# MAIN_SCH.net
KiCad netlist of a schematic drawn in Altium Designer
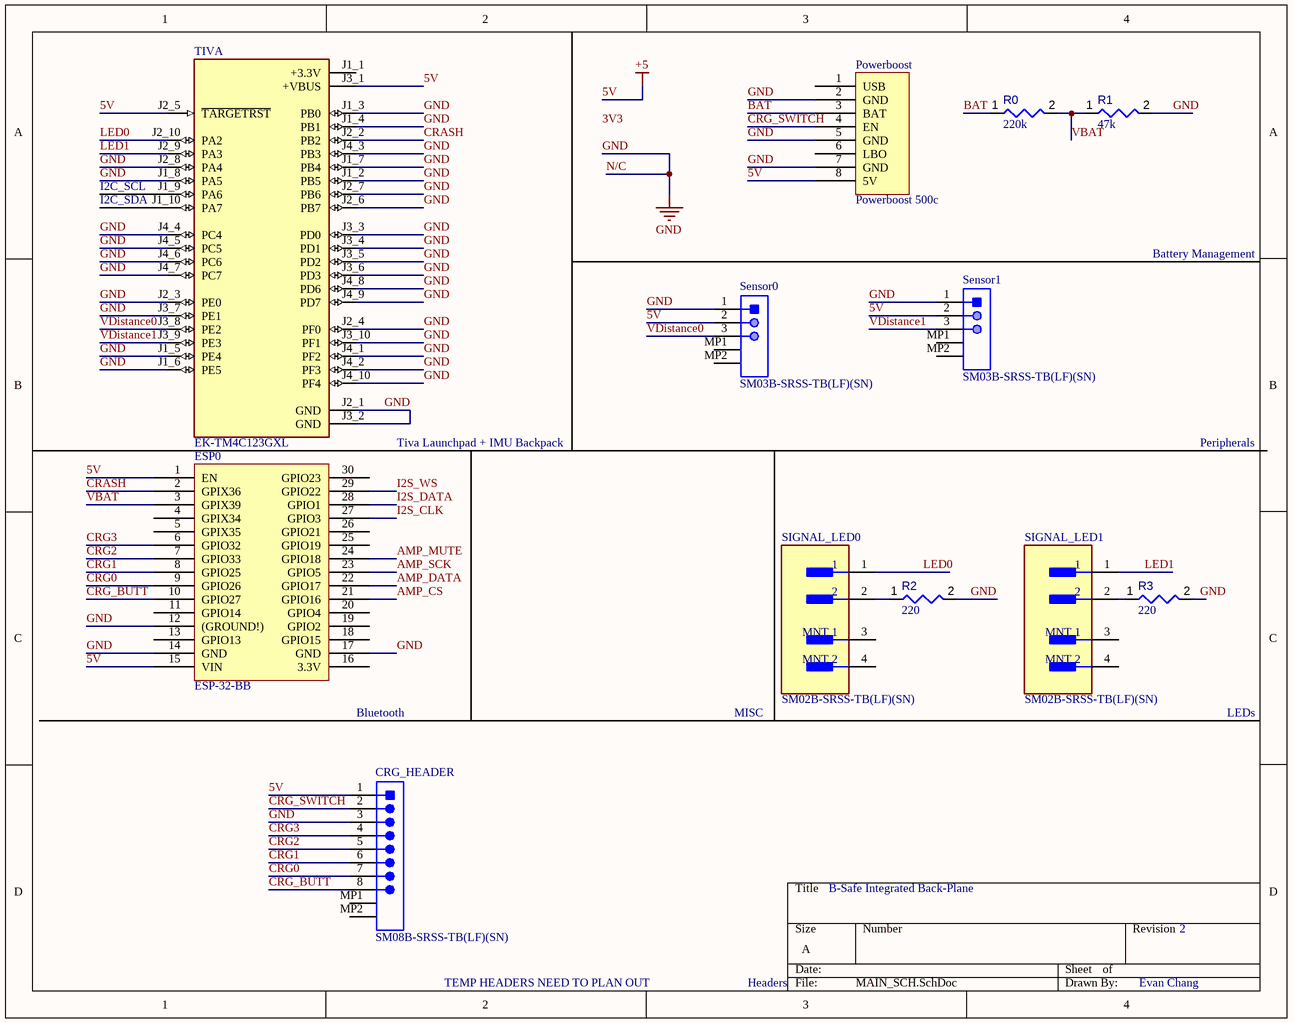
[diagram p0: MAIN_SCH.SchDoc]

(export (version "E")
  (design (tool "Eeschema 10.0.6"))
  (components
    (comp (ref "CRG_HEADER")
      (value "SM08B-SRSS-TB(LF)(SN)")
      (footprint "JST-SM08B-SRSS-TB_V")
      (description "Connector Header, Side Entry, SR Series, 8 Position, 1.00mm, 50V, Surface Mount, Tin, Natural")
      (libsource (lib "Evan Chang work on PCB") (part "CN-1P-2M-R8"))
    )
    (comp (ref "ESP0")
      (value "ESP-32-BB")
      (footprint "ESP-32-BB-Footprint-1")
      (description "Breakoutboard for ESP-32-BB")
      (libsource (lib "Evan Chang work on PCB") (part "ESP-32-BB-Symbol-1"))
    )
    (comp (ref "Powerboost")
      (value "Powerboost 500c")
      (footprint "Powerboost 500c-Footprint-1")
      (description "Breakout board component for Adafruit Powerboost 500c")
      (libsource (lib "Evan Chang work on PCB") (part "Powerboost 500c-Symbol-1"))
    )
    (comp (ref "R0")
      (value "220k")
      (footprint "RESC1005X40X25NL05T10")
      (fields (field (name "TOLERANCE") "1%") (field (name "Comment") "RC0402FR-07220KL"))
      (libsource (lib "Evan Chang work on PCB") (part "RES-2"))
    )
    (comp (ref "R1")
      (value "47k")
      (footprint "RESC1005X40X25NL05T10")
      (fields (field (name "TOLERANCE") "1%") (field (name "Comment") "RC0402FR-0747KL"))
      (libsource (lib "Evan Chang work on PCB") (part "RES-2"))
    )
    (comp (ref "R2")
      (value "220")
      (footprint "RESC1608X55X30LL20T10")
      (fields (field (name "TOLERANCE") "5%") (field (name "Comment") "RK73B1JTTD221J"))
      (libsource (lib "Evan Chang work on PCB") (part "RES-2"))
    )
    (comp (ref "R3")
      (value "220")
      (footprint "RESC1608X55X30LL20T10")
      (fields (field (name "TOLERANCE") "5%") (field (name "Comment") "RK73B1JTTD221J"))
      (libsource (lib "Evan Chang work on PCB") (part "RES-2"))
    )
    (comp (ref "Sensor0")
      (value "SM03B-SRSS-TB(LF)(SN)")
      (footprint "JST-SM03B-SRSS-TB_V")
      (description "CONN HEADER SH 3POS SIDE 1MM TIN")
      (libsource (lib "Evan Chang work on PCB") (part "CN-1P-2M-R3"))
    )
    (comp (ref "Sensor1")
      (value "SM03B-SRSS-TB(LF)(SN)")
      (footprint "JST-SM03B-SRSS-TB_V")
      (description "CONN HEADER SH 3POS SIDE 1MM TIN")
      (libsource (lib "Evan Chang work on PCB") (part "CN-1P-2M-R3"))
    )
    (comp (ref "SIGNAL_LED0")
      (value "SM02B-SRSS-TB(LF)(SN)")
      (footprint "FP-SM02B-SRSS-TB_LF_SN-0")
      (description "CONN HEADER SH 2POS SIDE 1MM TIN")
      (libsource (lib "Evan Chang work on PCB") (part "e34efe21362d63d7198b5d2c73e37bd"))
    )
    (comp (ref "SIGNAL_LED1")
      (value "SM02B-SRSS-TB(LF)(SN)")
      (footprint "FP-SM02B-SRSS-TB_LF_SN-0")
      (description "CONN HEADER SH 2POS SIDE 1MM TIN")
      (libsource (lib "Evan Chang work on PCB") (part "e34efe21362d63d7198b5d2c73e37bd"))
    )
    (comp (ref "TIVA")
      (value "EK-TM4C123GXL")
      (footprint "EK-TM4C123GXL-Footprint-1")
      (description "ARMÂ® CortexÂ®-M4F Based MCU TM4C123G LaunchPadâ„¢ Evaluation Kit")
      (fields (field (name "MF") "Texas Instruments"))
      (libsource (lib "Evan Chang work on PCB") (part "EK-TM4C123GXL"))
    )
  )
  (nets
    (net (code "1") (name "+5") (class "Default")
      (node (ref "CRG_HEADER") (pin "1") (pinfunction "1_1") (pintype "passive"))
      (node (ref "ESP0") (pin "1") (pinfunction "EN_1") (pintype "passive"))
      (node (ref "ESP0") (pin "15") (pinfunction "VIN_15") (pintype "power_in"))
      (node (ref "Powerboost") (pin "8") (pinfunction "5V_8") (pintype "power_in"))
      (node (ref "Sensor0") (pin "2") (pinfunction "2_2") (pintype "passive"))
      (node (ref "Sensor1") (pin "2") (pinfunction "2_2") (pintype "passive"))
      (node (ref "TIVA") (pin "J2_5") (pinfunction "~{TARGETRST}_J2_5") (pintype "input"))
      (node (ref "TIVA") (pin "J3_1") (pinfunction "+VBUS_J3_1") (pintype "power_in"))
    )
    (net (code "3") (name "/AMP_CS") (class "Default")
      (node (ref "ESP0") (pin "21") (pinfunction "GPIO16_21") (pintype "passive"))
    )
    (net (code "4") (name "/AMP_DATA") (class "Default")
      (node (ref "ESP0") (pin "22") (pinfunction "GPIO17_22") (pintype "passive"))
    )
    (net (code "5") (name "/AMP_MUTE") (class "Default")
      (node (ref "ESP0") (pin "24") (pinfunction "GPIO18_24") (pintype "passive"))
    )
    (net (code "6") (name "/AMP_SCK") (class "Default")
      (node (ref "ESP0") (pin "23") (pinfunction "GPIO5_23") (pintype "passive"))
    )
    (net (code "7") (name "/BAT") (class "Default")
      (node (ref "Powerboost") (pin "3") (pinfunction "BAT_3") (pintype "passive"))
      (node (ref "R0") (pin "1") (pinfunction "1_1") (pintype "passive"))
    )
    (net (code "8") (name "/CRASH") (class "Default")
      (node (ref "ESP0") (pin "2") (pinfunction "GPIX36_2") (pintype "passive"))
      (node (ref "TIVA") (pin "J2_2") (pinfunction "PB2_J2_2") (pintype "bidirectional"))
    )
    (net (code "9") (name "/CRG0") (class "Default")
      (node (ref "CRG_HEADER") (pin "7") (pinfunction "7_7") (pintype "passive"))
      (node (ref "ESP0") (pin "9") (pinfunction "GPIO26_9") (pintype "passive"))
    )
    (net (code "10") (name "/CRG1") (class "Default")
      (node (ref "CRG_HEADER") (pin "6") (pinfunction "6_6") (pintype "passive"))
      (node (ref "ESP0") (pin "8") (pinfunction "GPIO25_8") (pintype "passive"))
    )
    (net (code "11") (name "/CRG2") (class "Default")
      (node (ref "CRG_HEADER") (pin "5") (pinfunction "5_5") (pintype "passive"))
      (node (ref "ESP0") (pin "7") (pinfunction "GPIO33_7") (pintype "passive"))
    )
    (net (code "12") (name "/CRG3") (class "Default")
      (node (ref "CRG_HEADER") (pin "4") (pinfunction "4_4") (pintype "passive"))
      (node (ref "ESP0") (pin "6") (pinfunction "GPIO32_6") (pintype "passive"))
    )
    (net (code "13") (name "/CRG_BUTT") (class "Default")
      (node (ref "CRG_HEADER") (pin "8") (pinfunction "8_8") (pintype "passive"))
      (node (ref "ESP0") (pin "10") (pinfunction "GPIO27_10") (pintype "passive"))
    )
    (net (code "14") (name "/CRG_SWITCH") (class "Default")
      (node (ref "CRG_HEADER") (pin "2") (pinfunction "2_2") (pintype "passive"))
      (node (ref "Powerboost") (pin "4") (pinfunction "EN_4") (pintype "passive"))
    )
    (net (code "15") (name "/I2S_CLK") (class "Default")
      (node (ref "ESP0") (pin "27") (pinfunction "GPIO3_27") (pintype "passive"))
    )
    (net (code "16") (name "/I2S_DATA") (class "Default")
      (node (ref "ESP0") (pin "28") (pinfunction "GPIO1_28") (pintype "passive"))
    )
    (net (code "17") (name "/I2S_WS") (class "Default")
      (node (ref "ESP0") (pin "29") (pinfunction "GPIO22_29") (pintype "passive"))
    )
    (net (code "18") (name "/LED0") (class "Default")
      (node (ref "SIGNAL_LED0") (pin "1") (pinfunction "1_1") (pintype "passive"))
      (node (ref "TIVA") (pin "J2_10") (pinfunction "PA2_J2_10") (pintype "bidirectional"))
    )
    (net (code "19") (name "/LED1") (class "Default")
      (node (ref "SIGNAL_LED1") (pin "1") (pinfunction "1_1") (pintype "passive"))
      (node (ref "TIVA") (pin "J2_9") (pinfunction "PA3_J2_9") (pintype "bidirectional"))
    )
    (net (code "20") (name "/VBAT") (class "Default")
      (node (ref "ESP0") (pin "3") (pinfunction "GPIX39_3") (pintype "passive"))
      (node (ref "R0") (pin "2") (pinfunction "2_2") (pintype "passive"))
      (node (ref "R1") (pin "1") (pinfunction "1_1") (pintype "passive"))
    )
    (net (code "21") (name "/VDistance0") (class "Default")
      (node (ref "Sensor0") (pin "3") (pinfunction "3_3") (pintype "passive"))
      (node (ref "TIVA") (pin "J3_8") (pinfunction "PE2_J3_8") (pintype "bidirectional"))
    )
    (net (code "22") (name "/VDistance1") (class "Default")
      (node (ref "Sensor1") (pin "3") (pinfunction "3_3") (pintype "passive"))
      (node (ref "TIVA") (pin "J3_9") (pinfunction "PE3_J3_9") (pintype "bidirectional"))
    )
    (net (code "23") (name "GND") (class "Default")
      (node (ref "CRG_HEADER") (pin "3") (pinfunction "3_3") (pintype "passive"))
      (node (ref "ESP0") (pin "12") (pinfunction "(GROUND!)_12") (pintype "passive"))
      (node (ref "ESP0") (pin "14") (pinfunction "GND_14") (pintype "power_in"))
      (node (ref "ESP0") (pin "17") (pinfunction "GND_17") (pintype "power_in"))
      (node (ref "Powerboost") (pin "2") (pinfunction "GND_2") (pintype "power_in"))
      (node (ref "Powerboost") (pin "5") (pinfunction "GND_5") (pintype "power_in"))
      (node (ref "Powerboost") (pin "7") (pinfunction "GND_7") (pintype "power_in"))
      (node (ref "R1") (pin "2") (pinfunction "2_2") (pintype "passive"))
      (node (ref "R2") (pin "2") (pinfunction "2_2") (pintype "passive"))
      (node (ref "R3") (pin "2") (pinfunction "2_2") (pintype "passive"))
      (node (ref "Sensor0") (pin "1") (pinfunction "1_1") (pintype "passive"))
      (node (ref "Sensor1") (pin "1") (pinfunction "1_1") (pintype "passive"))
      (node (ref "TIVA") (pin "J1_2") (pinfunction "PB5_J1_2") (pintype "bidirectional"))
      (node (ref "TIVA") (pin "J1_3") (pinfunction "PB0_J1_3") (pintype "bidirectional"))
      (node (ref "TIVA") (pin "J1_4") (pinfunction "PB1_J1_4") (pintype "bidirectional"))
      (node (ref "TIVA") (pin "J1_5") (pinfunction "PE4_J1_5") (pintype "bidirectional"))
      (node (ref "TIVA") (pin "J1_6") (pinfunction "PE5_J1_6") (pintype "bidirectional"))
      (node (ref "TIVA") (pin "J1_7") (pinfunction "PB4_J1_7") (pintype "bidirectional"))
      (node (ref "TIVA") (pin "J1_8") (pinfunction "PA5_J1_8") (pintype "bidirectional"))
      (node (ref "TIVA") (pin "J2_1") (pinfunction "GND_J2_1") (pintype "power_in"))
      (node (ref "TIVA") (pin "J2_3") (pinfunction "PE0_J2_3") (pintype "bidirectional"))
      (node (ref "TIVA") (pin "J2_4") (pinfunction "PF0_J2_4") (pintype "bidirectional"))
      (node (ref "TIVA") (pin "J2_6") (pinfunction "PB7_J2_6") (pintype "bidirectional"))
      (node (ref "TIVA") (pin "J2_7") (pinfunction "PB6_J2_7") (pintype "bidirectional"))
      (node (ref "TIVA") (pin "J2_8") (pinfunction "PA4_J2_8") (pintype "bidirectional"))
      (node (ref "TIVA") (pin "J3_10") (pinfunction "PF1_J3_10") (pintype "bidirectional"))
      (node (ref "TIVA") (pin "J3_2") (pinfunction "GND_J3_2") (pintype "power_in"))
      (node (ref "TIVA") (pin "J3_3") (pinfunction "PD0_J3_3") (pintype "bidirectional"))
      (node (ref "TIVA") (pin "J3_4") (pinfunction "PD1_J3_4") (pintype "bidirectional"))
      (node (ref "TIVA") (pin "J3_5") (pinfunction "PD2_J3_5") (pintype "bidirectional"))
      (node (ref "TIVA") (pin "J3_6") (pinfunction "PD3_J3_6") (pintype "bidirectional"))
      (node (ref "TIVA") (pin "J3_7") (pinfunction "PE1_J3_7") (pintype "bidirectional"))
      (node (ref "TIVA") (pin "J4_1") (pinfunction "PF2_J4_1") (pintype "bidirectional"))
      (node (ref "TIVA") (pin "J4_10") (pinfunction "PF4_J4_10") (pintype "bidirectional"))
      (node (ref "TIVA") (pin "J4_2") (pinfunction "PF3_J4_2") (pintype "bidirectional"))
      (node (ref "TIVA") (pin "J4_3") (pinfunction "PB3_J4_3") (pintype "bidirectional"))
      (node (ref "TIVA") (pin "J4_4") (pinfunction "PC4_J4_4") (pintype "bidirectional"))
      (node (ref "TIVA") (pin "J4_5") (pinfunction "PC5_J4_5") (pintype "bidirectional"))
      (node (ref "TIVA") (pin "J4_6") (pinfunction "PC6_J4_6") (pintype "bidirectional"))
      (node (ref "TIVA") (pin "J4_7") (pinfunction "PC7_J4_7") (pintype "bidirectional"))
      (node (ref "TIVA") (pin "J4_8") (pinfunction "PD6_J4_8") (pintype "bidirectional"))
      (node (ref "TIVA") (pin "J4_9") (pinfunction "PD7_J4_9") (pintype "bidirectional"))
    )
    (net (code "24") (name "Net-(R2-Pad1)") (class "Default")
      (node (ref "R2") (pin "1") (pinfunction "1_1") (pintype "passive"))
      (node (ref "SIGNAL_LED0") (pin "2") (pinfunction "2_2") (pintype "passive"))
    )
    (net (code "25") (name "Net-(R3-Pad1)") (class "Default")
      (node (ref "R3") (pin "1") (pinfunction "1_1") (pintype "passive"))
      (node (ref "SIGNAL_LED1") (pin "2") (pinfunction "2_2") (pintype "passive"))
    )
    (net (code "26") (name "unconnected-(CRG_HEADER-PadMP1)") (class "Default")
      (node (ref "CRG_HEADER") (pin "MP1") (pinfunction "MP1_MP1") (pintype "passive"))
    )
    (net (code "27") (name "unconnected-(CRG_HEADER-PadMP2)") (class "Default")
      (node (ref "CRG_HEADER") (pin "MP2") (pinfunction "MP2_MP2") (pintype "passive"))
    )
    (net (code "28") (name "unconnected-(ESP0-3.3V-Pad16)") (class "Default")
      (node (ref "ESP0") (pin "16") (pinfunction "3.3V_16") (pintype "passive"))
    )
    (net (code "29") (name "unconnected-(ESP0-GPIO2-Pad19)") (class "Default")
      (node (ref "ESP0") (pin "19") (pinfunction "GPIO2_19") (pintype "passive"))
    )
    (net (code "30") (name "unconnected-(ESP0-GPIO4-Pad20)") (class "Default")
      (node (ref "ESP0") (pin "20") (pinfunction "GPIO4_20") (pintype "passive"))
    )
    (net (code "31") (name "unconnected-(ESP0-GPIO13-Pad13)") (class "Default")
      (node (ref "ESP0") (pin "13") (pinfunction "GPIO13_13") (pintype "passive"))
    )
    (net (code "32") (name "unconnected-(ESP0-GPIO14-Pad11)") (class "Default")
      (node (ref "ESP0") (pin "11") (pinfunction "GPIO14_11") (pintype "passive"))
    )
    (net (code "33") (name "unconnected-(ESP0-GPIO15-Pad18)") (class "Default")
      (node (ref "ESP0") (pin "18") (pinfunction "GPIO15_18") (pintype "passive"))
    )
    (net (code "34") (name "unconnected-(ESP0-GPIO19-Pad25)") (class "Default")
      (node (ref "ESP0") (pin "25") (pinfunction "GPIO19_25") (pintype "passive"))
    )
    (net (code "35") (name "unconnected-(ESP0-GPIO21-Pad26)") (class "Default")
      (node (ref "ESP0") (pin "26") (pinfunction "GPIO21_26") (pintype "passive"))
    )
    (net (code "36") (name "unconnected-(ESP0-GPIO23-Pad30)") (class "Default")
      (node (ref "ESP0") (pin "30") (pinfunction "GPIO23_30") (pintype "passive"))
    )
    (net (code "37") (name "unconnected-(ESP0-GPIX34-Pad4)") (class "Default")
      (node (ref "ESP0") (pin "4") (pinfunction "GPIX34_4") (pintype "passive"))
    )
    (net (code "38") (name "unconnected-(ESP0-GPIX35-Pad5)") (class "Default")
      (node (ref "ESP0") (pin "5") (pinfunction "GPIX35_5") (pintype "passive"))
    )
    (net (code "39") (name "unconnected-(Powerboost-LBO-Pad6)") (class "Default")
      (node (ref "Powerboost") (pin "6") (pinfunction "LBO_6") (pintype "passive"))
    )
    (net (code "40") (name "unconnected-(Powerboost-USB-Pad1)") (class "Default")
      (node (ref "Powerboost") (pin "1") (pinfunction "USB_1") (pintype "passive"))
    )
    (net (code "41") (name "unconnected-(SIGNAL_LED0-MNT_1-Pad3)") (class "Default")
      (node (ref "SIGNAL_LED0") (pin "3") (pinfunction "MNT_1_3") (pintype "passive"))
    )
    (net (code "42") (name "unconnected-(SIGNAL_LED0-MNT_2-Pad4)") (class "Default")
      (node (ref "SIGNAL_LED0") (pin "4") (pinfunction "MNT_2_4") (pintype "passive"))
    )
    (net (code "43") (name "unconnected-(SIGNAL_LED1-MNT_1-Pad3)") (class "Default")
      (node (ref "SIGNAL_LED1") (pin "3") (pinfunction "MNT_1_3") (pintype "passive"))
    )
    (net (code "44") (name "unconnected-(SIGNAL_LED1-MNT_2-Pad4)") (class "Default")
      (node (ref "SIGNAL_LED1") (pin "4") (pinfunction "MNT_2_4") (pintype "passive"))
    )
    (net (code "45") (name "unconnected-(Sensor0-PadMP1)") (class "Default")
      (node (ref "Sensor0") (pin "MP1") (pinfunction "MP1_MP1") (pintype "passive"))
    )
    (net (code "46") (name "unconnected-(Sensor0-PadMP2)") (class "Default")
      (node (ref "Sensor0") (pin "MP2") (pinfunction "MP2_MP2") (pintype "passive"))
    )
    (net (code "47") (name "unconnected-(Sensor1-PadMP1)") (class "Default")
      (node (ref "Sensor1") (pin "MP1") (pinfunction "MP1_MP1") (pintype "passive"))
    )
    (net (code "48") (name "unconnected-(Sensor1-PadMP2)") (class "Default")
      (node (ref "Sensor1") (pin "MP2") (pinfunction "MP2_MP2") (pintype "passive"))
    )
    (net (code "49") (name "unconnected-(TIVA-+3.3V-PadJ1_1)") (class "Default")
      (node (ref "TIVA") (pin "J1_1") (pinfunction "+3.3V_J1_1") (pintype "power_in"))
    )
    (net (code "50") (name "unconnected-(TIVA-PA6-PadJ1_9)") (class "Default")
      (node (ref "TIVA") (pin "J1_9") (pinfunction "PA6_J1_9") (pintype "bidirectional"))
    )
    (net (code "51") (name "unconnected-(TIVA-PA7-PadJ1_10)") (class "Default")
      (node (ref "TIVA") (pin "J1_10") (pinfunction "PA7_J1_10") (pintype "bidirectional"))
    )
  )
)
